# Solar_950_test.net
KiCad netlist of a schematic drawn in Altium Designer
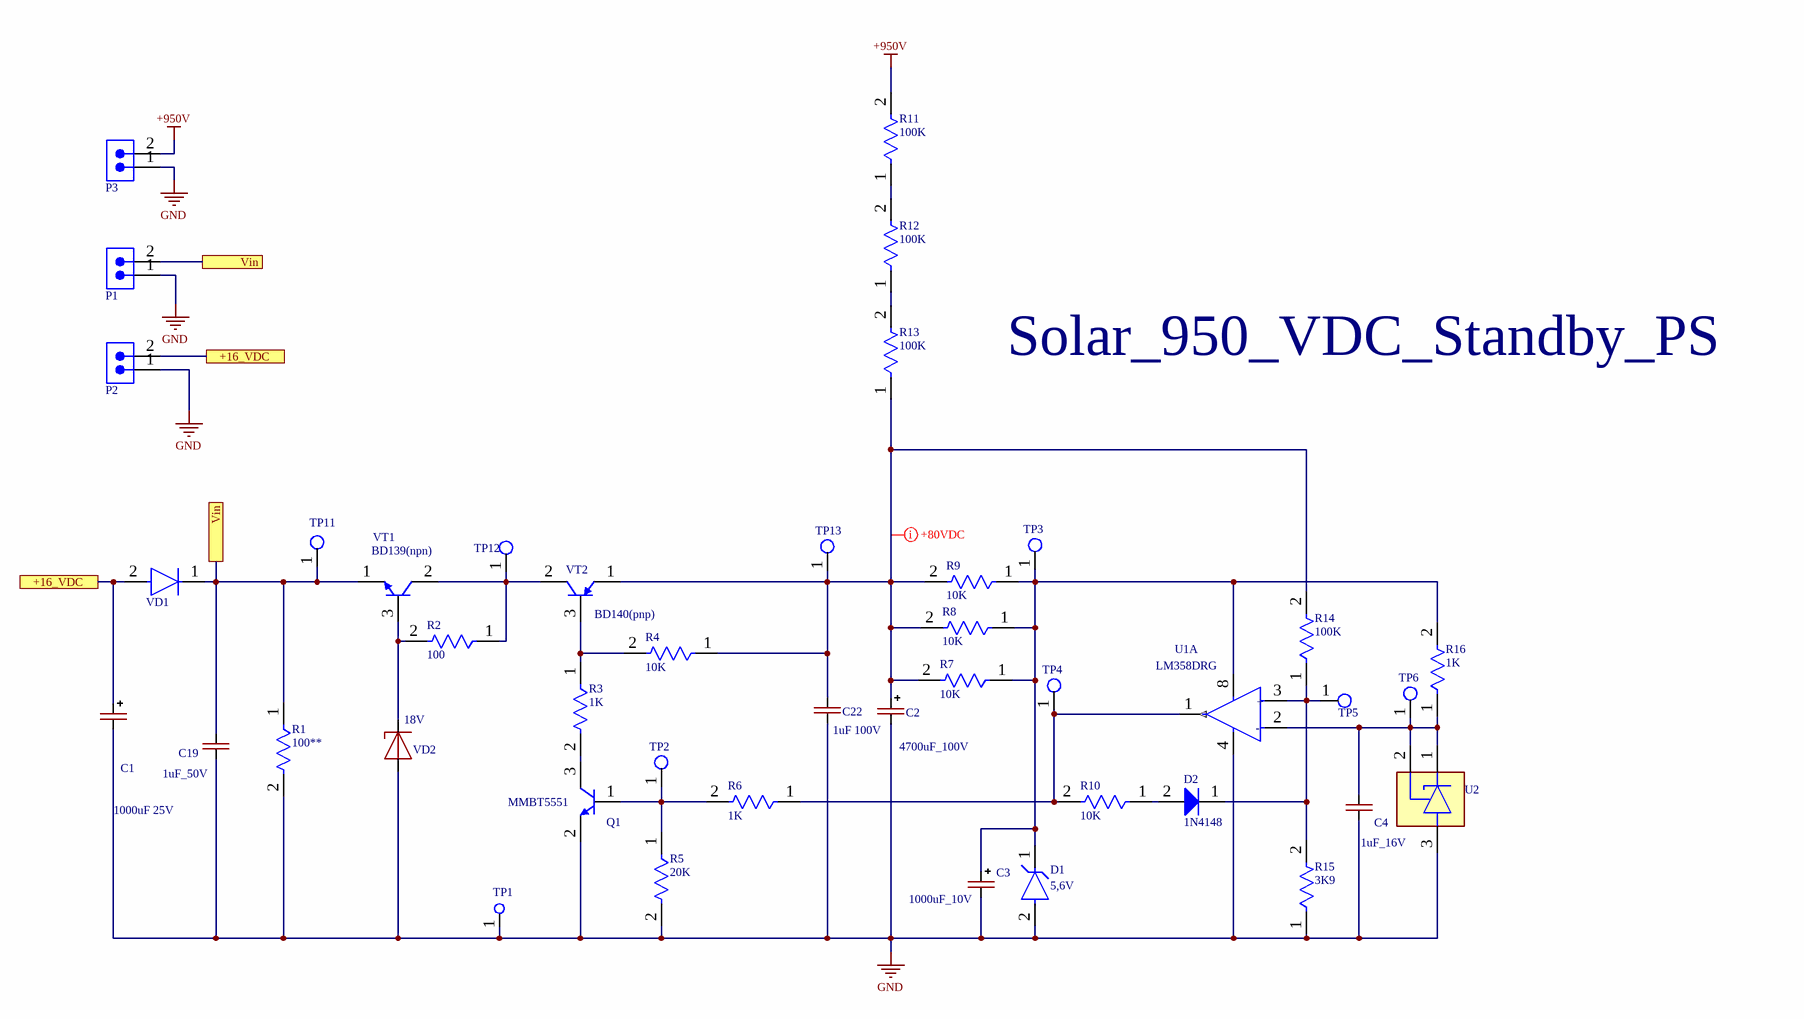
[diagram p0: Solar_950_test.SchDoc]

(export (version "E")
  (design (tool "Eeschema 10.0.6"))
  (components
    (comp (ref "C1")
      (value "1000uF 25V")
      (footprint "CAPPOL-12x25")
      (libsource (lib "PASSIVE_COMPONENTS") (part "CAP-POLAR"))
    )
    (comp (ref "C2")
      (value "4700uF_100V")
      (footprint "CAPPOL_35x60")
      (libsource (lib "PASSIVE_COMPONENTS") (part "CAP-POLAR"))
    )
    (comp (ref "C3")
      (value "1000uF_10V")
      (footprint "CAP_SMD_Size_E")
      (libsource (lib "PASSIVE_COMPONENTS") (part "CAP_POL_SMD"))
    )
    (comp (ref "C4")
      (value "1uF_16V")
      (footprint "CAP-0805")
      (libsource (lib "PASSIVE_COMPONENTS") (part "CAP-NON-POLAR"))
    )
    (comp (ref "C19")
      (value "1uF_50V")
      (footprint "CAP-0805")
      (libsource (lib "PASSIVE_COMPONENTS") (part "CAP-NON-POLAR"))
    )
    (comp (ref "C22")
      (value "1uF 100V")
      (footprint "CAP-0805")
      (libsource (lib "PASSIVE_COMPONENTS") (part "CAP-NON-POLAR"))
    )
    (comp (ref "D1")
      (value "5,6V")
      (footprint "FP-SB-V-3906_04-031_4-MFG")
      (description "DIODE ZENER 8.2V 500MW DO35")
      (fields (field (name "TOLERANCE") "2%"))
      (libsource (lib "Altium Content Vault") (part "f813f71cba58e380607f5dd3caf9714"))
    )
    (comp (ref "D2")
      (value "1N4148")
      (footprint "DIOD-SOD123-2_V")
      (libsource (lib "Diodes") (part "1N4148"))
    )
    (comp (ref "P1")
      (value "691701530002B")
      (footprint "691701530002B")
      (description "WR-TBL Series 7015B Open Horizontal PCB Header, SMT, pitch 5.08mm, 2p")
      (fields (field (name "MANUFACTURER") "Wurth Elektronik"))
      (libsource (lib "Altium_WR-TBL (rev23f)") (part "691701530002B"))
    )
    (comp (ref "P2")
      (value "691701530002B")
      (footprint "691701530002B")
      (description "WR-TBL Series 7015B Open Horizontal PCB Header, SMT, pitch 5.08mm, 2p")
      (fields (field (name "MANUFACTURER") "Wurth Elektronik"))
      (libsource (lib "Altium_WR-TBL (rev23f)") (part "691701530002B"))
    )
    (comp (ref "P3")
      (value "691701530002B")
      (footprint "691701530002B")
      (description "WR-TBL Series 7015B Open Horizontal PCB Header, SMT, pitch 5.08mm, 2p")
      (fields (field (name "MANUFACTURER") "Wurth Elektronik"))
      (libsource (lib "Altium_WR-TBL (rev23f)") (part "691701530002B"))
    )
    (comp (ref "Q1")
      (value "MMBT5551")
      (footprint "INF-SOT23_N")
      (description "NPN Silicon AF Transistor, 45 V VCEO, 100 mA IC, SOT23, Reel, Green")
      (fields (field (name "PARTNUMBER") "BC847C") (field (name "MANUFACTURER") "Infineon"))
      (libsource (lib "Transistors") (part "BC847C_Infineon"))
    )
    (comp (ref "R1")
      (value "100**")
      (footprint "RES-2512")
      (description "100")
      (libsource (lib "PASSIVE_COMPONENTS") (part "RES-CONST"))
    )
    (comp (ref "R2")
      (value "100")
      (footprint "RES-2512")
      (libsource (lib "PASSIVE_COMPONENTS") (part "RES-CONST"))
    )
    (comp (ref "R3")
      (value "1K")
      (footprint "RES-2512")
      (libsource (lib "PASSIVE_COMPONENTS") (part "RES-CONST"))
    )
    (comp (ref "R4")
      (value "10K")
      (footprint "RES-0805")
      (libsource (lib "PASSIVE_COMPONENTS") (part "RES-CONST"))
    )
    (comp (ref "R5")
      (value "20K")
      (footprint "RES-0805")
      (libsource (lib "PASSIVE_COMPONENTS") (part "RES-CONST"))
    )
    (comp (ref "R6")
      (value "1K")
      (footprint "RES-0805")
      (libsource (lib "PASSIVE_COMPONENTS") (part "RES-CONST"))
    )
    (comp (ref "R7")
      (value "10K")
      (footprint "RES-2512")
      (libsource (lib "PASSIVE_COMPONENTS") (part "RES-CONST"))
    )
    (comp (ref "R8")
      (value "10K")
      (footprint "RES-2512")
      (libsource (lib "PASSIVE_COMPONENTS") (part "RES-CONST"))
    )
    (comp (ref "R9")
      (value "10K")
      (footprint "RES-2512")
      (libsource (lib "PASSIVE_COMPONENTS") (part "RES-CONST"))
    )
    (comp (ref "R10")
      (value "10K")
      (footprint "RES-0805")
      (libsource (lib "PASSIVE_COMPONENTS") (part "RES-CONST"))
    )
    (comp (ref "R11")
      (value "100K")
      (footprint "RES-2512")
      (libsource (lib "PASSIVE_COMPONENTS") (part "RES-CONST"))
    )
    (comp (ref "R12")
      (value "100K")
      (footprint "RES-2512")
      (libsource (lib "PASSIVE_COMPONENTS") (part "RES-CONST"))
    )
    (comp (ref "R13")
      (value "100K")
      (footprint "RES-2512")
      (libsource (lib "PASSIVE_COMPONENTS") (part "RES-CONST"))
    )
    (comp (ref "R14")
      (value "100K")
      (footprint "RES-0805")
      (libsource (lib "PASSIVE_COMPONENTS") (part "RES-CONST"))
    )
    (comp (ref "R15")
      (value "3K9")
      (footprint "RES-0805")
      (libsource (lib "PASSIVE_COMPONENTS") (part "RES-CONST"))
    )
    (comp (ref "R16")
      (value "1K")
      (footprint "RES-0805")
      (libsource (lib "PASSIVE_COMPONENTS") (part "RES-CONST"))
    )
    (comp (ref "TP1")
      (value "Test_Point_PCB")
      (footprint "Pin_Test_Point(Pink)")
      (description "Test_Point")
      (libsource (lib "") (part "TP_PCB?_1"))
    )
    (comp (ref "TP2")
      (value "Test_Point_PCB")
      (footprint "Test_Point")
      (description "Test_Point")
      (libsource (lib "Test_Point") (part "TP_PCB?"))
    )
    (comp (ref "TP3")
      (value "Test_Point_PCB")
      (footprint "Test_Point")
      (description "Test_Point")
      (libsource (lib "Test_Point") (part "TP_PCB?"))
    )
    (comp (ref "TP4")
      (value "Test_Point_PCB")
      (footprint "Test_Point")
      (description "Test_Point")
      (libsource (lib "Test_Point") (part "TP_PCB?"))
    )
    (comp (ref "TP5")
      (value "Test_Point_PCB")
      (footprint "Test_Point")
      (description "Test_Point")
      (libsource (lib "Test_Point") (part "TP_PCB?"))
    )
    (comp (ref "TP6")
      (value "Test_Point_PCB")
      (footprint "Test_Point")
      (description "Test_Point")
      (libsource (lib "Test_Point") (part "TP_PCB?"))
    )
    (comp (ref "TP11")
      (value "~")
      (footprint "Test_Point")
      (description "Test_Point")
      (libsource (lib "Connectors") (part "TP_PCB?"))
    )
    (comp (ref "TP12")
      (value "Test_Point_PCB")
      (footprint "Test_Point")
      (description "Test_Point")
      (libsource (lib "Test_Point") (part "TP_PCB?"))
    )
    (comp (ref "TP13")
      (value "Test_Point_PCB")
      (footprint "Test_Point")
      (description "Test_Point")
      (libsource (lib "Test_Point") (part "TP_PCB?"))
    )
    (comp (ref "U1")
      (value "LM358DRG")
      (footprint "SO8-150")
      (libsource (lib "Integrated_Circuts") (part "LM358DRG"))
    )
    (comp (ref "U2")
      (value "~")
      (footprint "TL431_SOT-23-3(A)")
      (description "TL431_SOT-23-3")
      (libsource (lib "Diodes") (part "TL431_SOT-23-3"))
    )
    (comp (ref "VD1") (value "US1G") (footprint "US1G_SMA") (libsource (lib "Diodes") (part "US1G")))
    (comp (ref "VD2") (value "18V") (footprint "DO-201") (libsource (lib "DO-201_ZENER") (part "ZENER")))
    (comp (ref "VT1")
      (value "BD139(npn)")
      (footprint "TO-126(bend2)")
      (libsource (lib "Transistors") (part "BD139"))
    )
    (comp (ref "VT2")
      (value "BD140(pnp)")
      (footprint "TO-126")
      (libsource (lib "Transistors") (part "BD140"))
    )
  )
  (nets
    (net (code "1") (name "+950V") (class "Default")
      (node (ref "P3") (pin "2") (pinfunction "2_2") (pintype "passive"))
      (node (ref "R11") (pin "2") (pinfunction "2_2") (pintype "passive"))
    )
    (net (code "2") (name "/+16_VDC") (class "Default")
      (node (ref "C1") (pin "1") (pinfunction "+_1") (pintype "passive"))
      (node (ref "P2") (pin "2") (pinfunction "2_2") (pintype "passive"))
      (node (ref "VD1") (pin "2") (pinfunction "A_2") (pintype "passive"))
    )
    (net (code "3") (name "/Vin") (class "Default")
      (node (ref "C19") (pin "1") (pinfunction "1_1") (pintype "passive"))
      (node (ref "P1") (pin "2") (pinfunction "2_2") (pintype "passive"))
      (node (ref "R1") (pin "1") (pinfunction "1_1") (pintype "passive"))
      (node (ref "TP11") (pin "1") (pinfunction "G9_1") (pintype "passive"))
      (node (ref "VD1") (pin "1") (pinfunction "C_1") (pintype "passive"))
      (node (ref "VT1") (pin "1") (pinfunction "E_1") (pintype "passive"))
    )
    (net (code "4") (name "GND") (class "Default")
      (node (ref "C1") (pin "2") (pinfunction "-_2") (pintype "passive"))
      (node (ref "C19") (pin "2") (pinfunction "2_2") (pintype "passive"))
      (node (ref "C2") (pin "2") (pinfunction "-_2") (pintype "passive"))
      (node (ref "C22") (pin "1") (pinfunction "1_1") (pintype "passive"))
      (node (ref "C3") (pin "2") (pinfunction "-_2") (pintype "passive"))
      (node (ref "C4") (pin "1") (pinfunction "1_1") (pintype "passive"))
      (node (ref "D1") (pin "2") (pinfunction "A_2") (pintype "passive"))
      (node (ref "P1") (pin "1") (pinfunction "1_1") (pintype "passive"))
      (node (ref "P2") (pin "1") (pinfunction "1_1") (pintype "passive"))
      (node (ref "P3") (pin "1") (pinfunction "1_1") (pintype "passive"))
      (node (ref "Q1") (pin "2") (pinfunction "E_2") (pintype "passive"))
      (node (ref "R1") (pin "2") (pinfunction "2_2") (pintype "passive"))
      (node (ref "R15") (pin "1") (pinfunction "1_1") (pintype "passive"))
      (node (ref "R5") (pin "2") (pinfunction "2_2") (pintype "passive"))
      (node (ref "TP1") (pin "1") (pinfunction "G9_1") (pintype "passive"))
      (node (ref "U1") (pin "4") (pinfunction "VEE/GND_4") (pintype "power_in"))
      (node (ref "U2") (pin "3") (pinfunction "A_3") (pintype "passive"))
      (node (ref "VD2") (pin "2") (pinfunction "A_2") (pintype "passive"))
    )
    (net (code "5") (name "Net-(C2-+)") (class "Default")
      (node (ref "C2") (pin "1") (pinfunction "+_1") (pintype "passive"))
      (node (ref "C22") (pin "2") (pinfunction "2_2") (pintype "passive"))
      (node (ref "R13") (pin "1") (pinfunction "1_1") (pintype "passive"))
      (node (ref "R14") (pin "2") (pinfunction "2_2") (pintype "passive"))
      (node (ref "R4") (pin "1") (pinfunction "1_1") (pintype "passive"))
      (node (ref "R7") (pin "2") (pinfunction "2_2") (pintype "passive"))
      (node (ref "R8") (pin "2") (pinfunction "2_2") (pintype "passive"))
      (node (ref "R9") (pin "2") (pinfunction "2_2") (pintype "passive"))
      (node (ref "TP13") (pin "1") (pinfunction "G9_1") (pintype "passive"))
      (node (ref "VT2") (pin "1") (pinfunction "E_1") (pintype "passive"))
    )
    (net (code "6") (name "Net-(C3-+)") (class "Default")
      (node (ref "C3") (pin "1") (pinfunction "+_1") (pintype "passive"))
      (node (ref "D1") (pin "1") (pinfunction "C_1") (pintype "passive"))
      (node (ref "R16") (pin "2") (pinfunction "2_2") (pintype "passive"))
      (node (ref "R7") (pin "1") (pinfunction "1_1") (pintype "passive"))
      (node (ref "R8") (pin "1") (pinfunction "1_1") (pintype "passive"))
      (node (ref "R9") (pin "1") (pinfunction "1_1") (pintype "passive"))
      (node (ref "TP3") (pin "1") (pinfunction "G9_1") (pintype "passive"))
      (node (ref "U1") (pin "8") (pinfunction "VCC_8") (pintype "power_in"))
    )
    (net (code "7") (name "Net-(D2-A)") (class "Default")
      (node (ref "D2") (pin "2") (pinfunction "A_2") (pintype "passive"))
      (node (ref "R10") (pin "1") (pinfunction "1_1") (pintype "passive"))
    )
    (net (code "8") (name "Net-(D2-K)") (class "Default")
      (node (ref "D2") (pin "1") (pinfunction "K_1") (pintype "passive"))
      (node (ref "R14") (pin "1") (pinfunction "1_1") (pintype "passive"))
      (node (ref "R15") (pin "2") (pinfunction "2_2") (pintype "passive"))
      (node (ref "TP5") (pin "1") (pinfunction "G9_1") (pintype "passive"))
      (node (ref "U1") (pin "3") (pinfunction "INPUT_A+_3") (pintype "tri_state"))
    )
    (net (code "9") (name "Net-(Q1-B)") (class "Default")
      (node (ref "Q1") (pin "1") (pinfunction "B_1") (pintype "passive"))
      (node (ref "R5") (pin "1") (pinfunction "1_1") (pintype "passive"))
      (node (ref "R6") (pin "2") (pinfunction "2_2") (pintype "passive"))
      (node (ref "TP2") (pin "1") (pinfunction "G9_1") (pintype "passive"))
    )
    (net (code "10") (name "Net-(Q1-C)") (class "Default")
      (node (ref "Q1") (pin "3") (pinfunction "C_3") (pintype "passive"))
      (node (ref "R3") (pin "2") (pinfunction "2_2") (pintype "passive"))
    )
    (net (code "11") (name "Net-(R11-Pad1)") (class "Default")
      (node (ref "R11") (pin "1") (pinfunction "1_1") (pintype "passive"))
      (node (ref "R12") (pin "2") (pinfunction "2_2") (pintype "passive"))
    )
    (net (code "12") (name "Net-(R12-Pad1)") (class "Default")
      (node (ref "R12") (pin "1") (pinfunction "1_1") (pintype "passive"))
      (node (ref "R13") (pin "2") (pinfunction "2_2") (pintype "passive"))
    )
    (net (code "13") (name "Net-(TP4-G9)") (class "Default")
      (node (ref "R10") (pin "2") (pinfunction "2_2") (pintype "passive"))
      (node (ref "R6") (pin "1") (pinfunction "1_1") (pintype "passive"))
      (node (ref "TP4") (pin "1") (pinfunction "G9_1") (pintype "passive"))
      (node (ref "U1") (pin "1") (pinfunction "OUTPUT_A_1") (pintype "output"))
    )
    (net (code "14") (name "Net-(TP6-G9)") (class "Default")
      (node (ref "C4") (pin "2") (pinfunction "2_2") (pintype "passive"))
      (node (ref "R16") (pin "1") (pinfunction "1_1") (pintype "passive"))
      (node (ref "TP6") (pin "1") (pinfunction "G9_1") (pintype "passive"))
      (node (ref "U1") (pin "2") (pinfunction "INPUT_A-_2") (pintype "tri_state"))
      (node (ref "U2") (pin "1") (pinfunction "C_1") (pintype "passive"))
      (node (ref "U2") (pin "2") (pinfunction "REF_2") (pintype "passive"))
    )
    (net (code "15") (name "Net-(TP12-G9)") (class "Default")
      (node (ref "R2") (pin "1") (pinfunction "1_1") (pintype "passive"))
      (node (ref "TP12") (pin "1") (pinfunction "G9_1") (pintype "passive"))
      (node (ref "VT1") (pin "2") (pinfunction "C_2") (pintype "passive"))
      (node (ref "VT2") (pin "2") (pinfunction "C_2") (pintype "passive"))
    )
    (net (code "16") (name "Net-(VD2-C)") (class "Default")
      (node (ref "R2") (pin "2") (pinfunction "2_2") (pintype "passive"))
      (node (ref "VD2") (pin "1") (pinfunction "C_1") (pintype "passive"))
      (node (ref "VT1") (pin "3") (pinfunction "B_3") (pintype "passive"))
    )
    (net (code "17") (name "Net-(VT2-B)") (class "Default")
      (node (ref "R3") (pin "1") (pinfunction "1_1") (pintype "passive"))
      (node (ref "R4") (pin "2") (pinfunction "2_2") (pintype "passive"))
      (node (ref "VT2") (pin "3") (pinfunction "B_3") (pintype "passive"))
    )
  )
)
